# MCU.net
KiCad netlist of a schematic drawn in Altium Designer
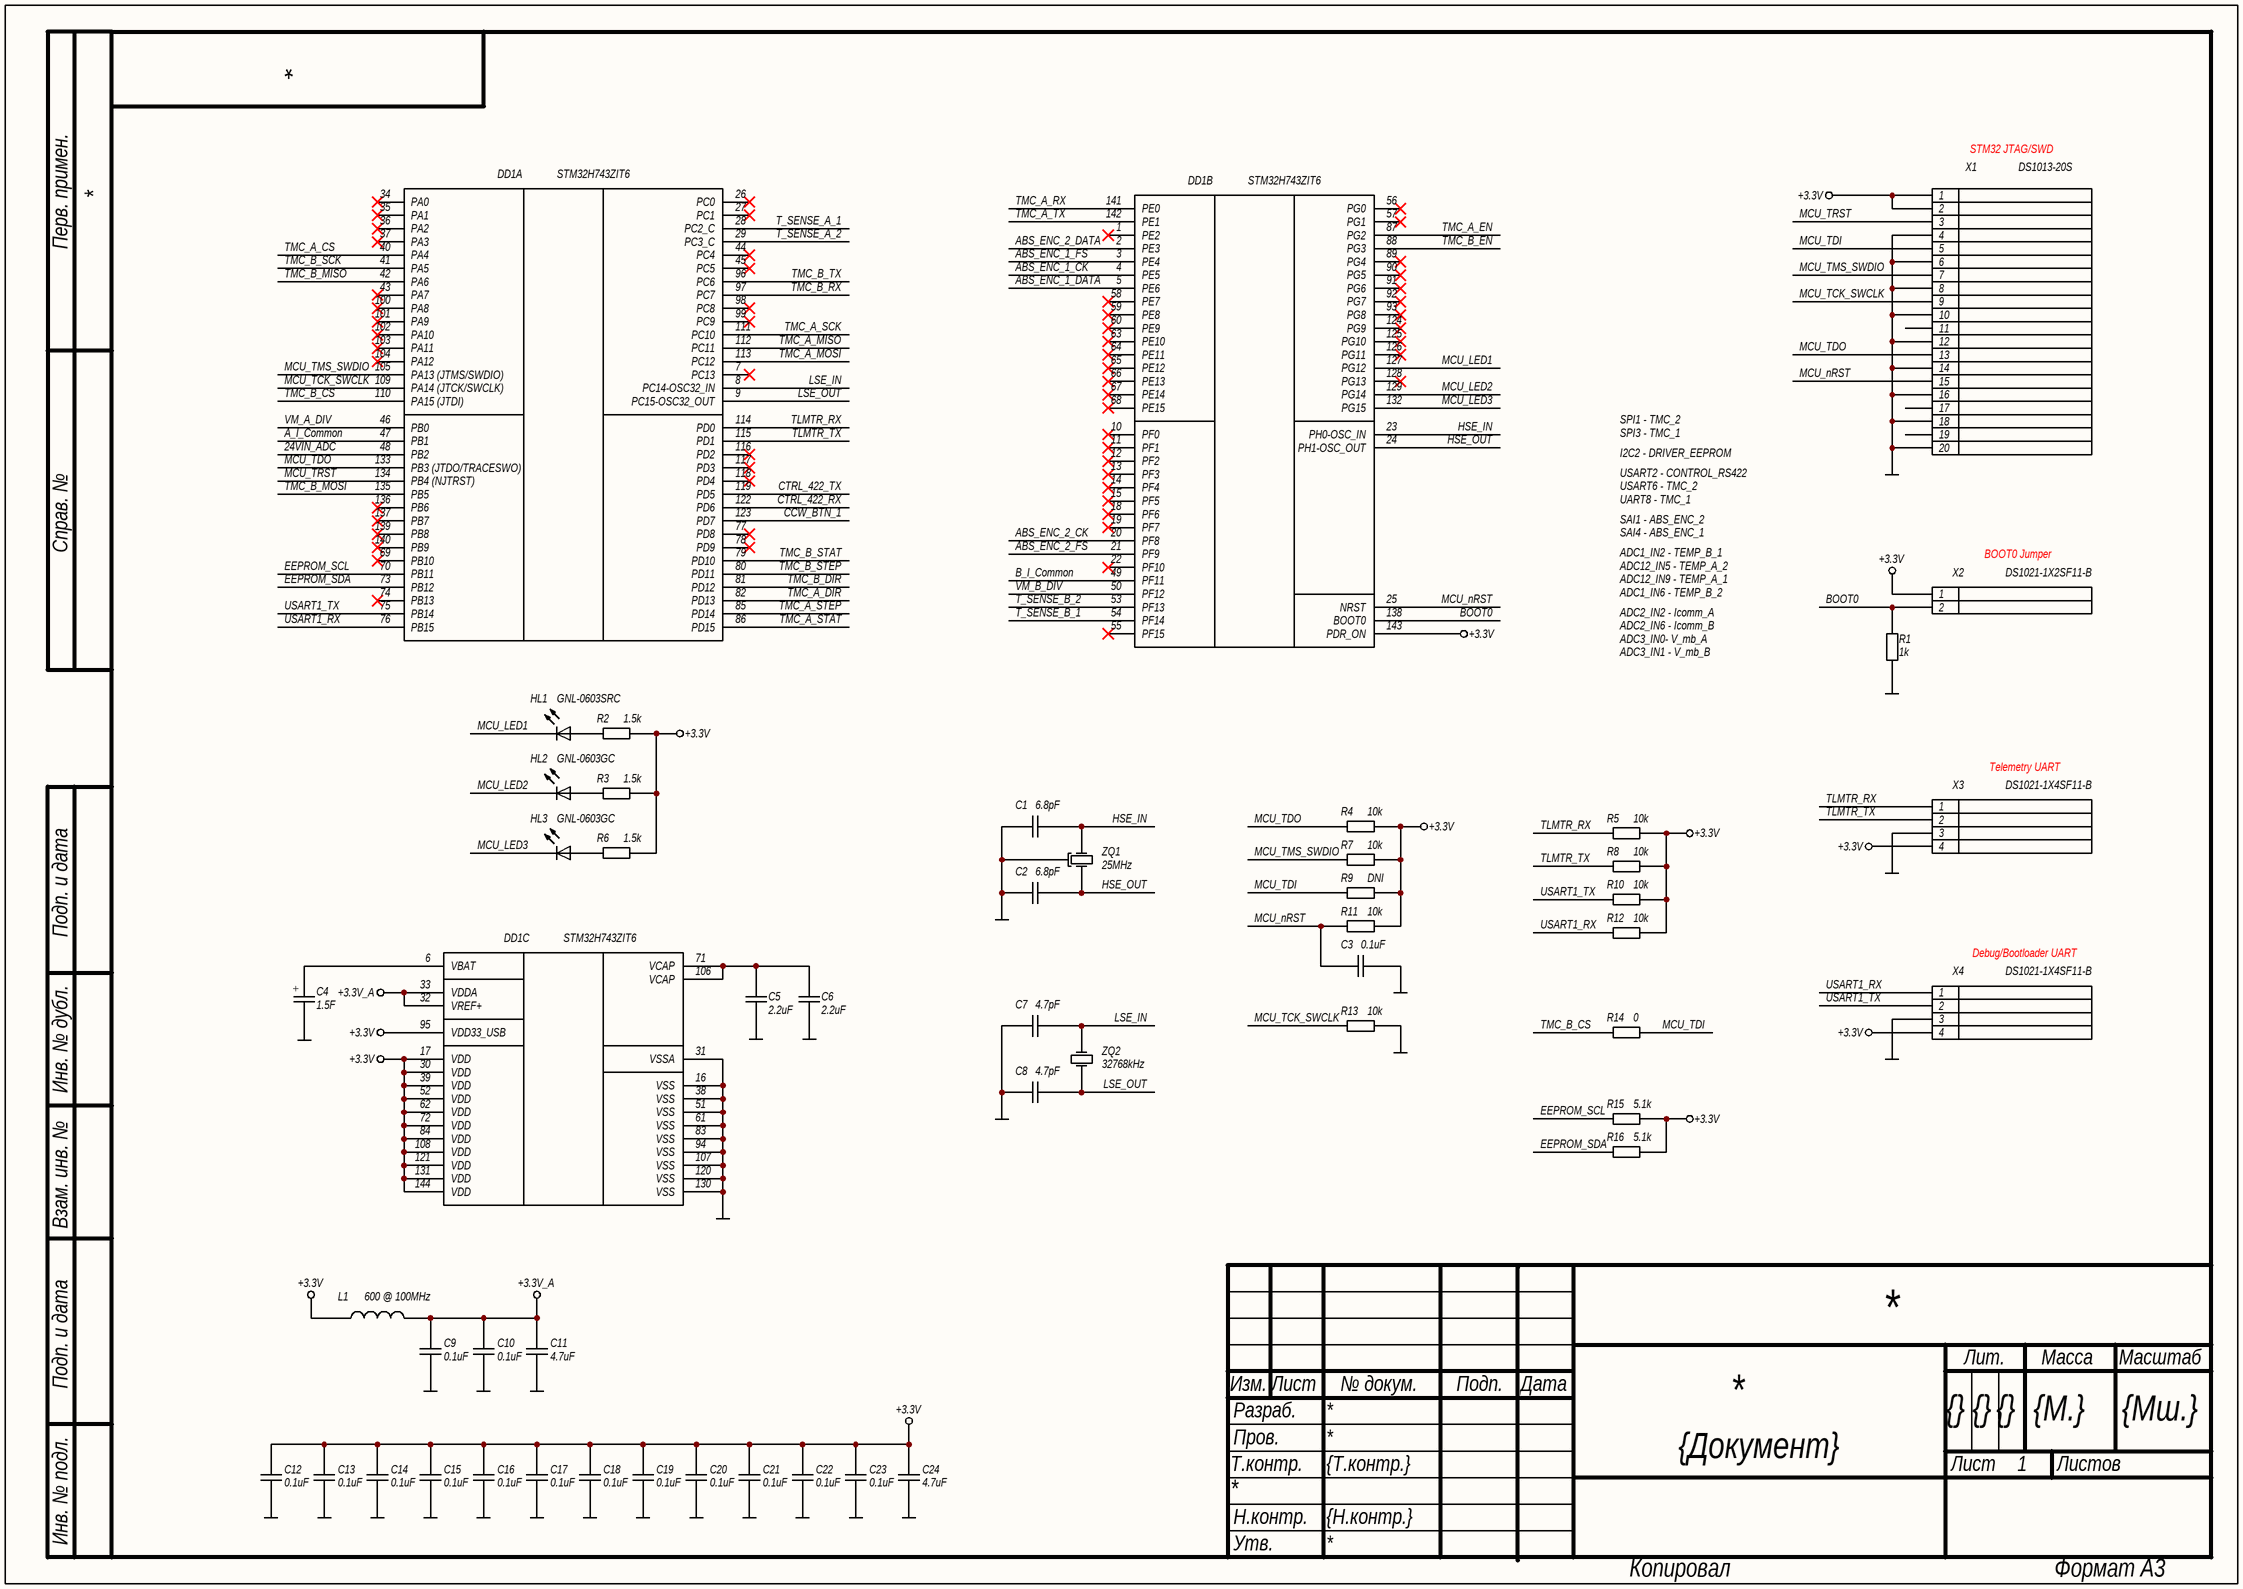
[diagram p0: MCU.SchDoc]

(export (version "E")
  (design (tool "Eeschema 10.0.6"))
  (components
    (comp (ref "C1")
      (value "6.8pF")
      (footprint "C0603N")
      (description "Конденсатор")
      (libsource (lib "Components Library") (part "CAP_FIXED"))
    )
    (comp (ref "C2")
      (value "6.8pF")
      (footprint "C0603N")
      (description "Конденсатор")
      (libsource (lib "Components Library") (part "CAP_FIXED"))
    )
    (comp (ref "C3")
      (value "0.1uF")
      (footprint "C0603N")
      (description "Конденсатор")
      (libsource (lib "Components Library") (part "CAP_FIXED"))
    )
    (comp (ref "C4")
      (value "1.5F")
      (footprint "KR-5R5H155-R")
      (description "Ионистор")
      (libsource (lib "Components Library") (part "CAP_EDLC"))
    )
    (comp (ref "C5")
      (value "2.2uF")
      (footprint "C0603N")
      (description "Конденсатор")
      (libsource (lib "Components Library") (part "CAP_FIXED"))
    )
    (comp (ref "C6")
      (value "2.2uF")
      (footprint "C0603N")
      (description "Конденсатор")
      (libsource (lib "Components Library") (part "CAP_FIXED"))
    )
    (comp (ref "C7")
      (value "4.7pF")
      (footprint "C0603N")
      (description "Конденсатор")
      (libsource (lib "Components Library") (part "CAP_FIXED"))
    )
    (comp (ref "C8")
      (value "4.7pF")
      (footprint "C0603N")
      (description "Конденсатор")
      (libsource (lib "Components Library") (part "CAP_FIXED"))
    )
    (comp (ref "C9")
      (value "0.1uF")
      (footprint "C0603N")
      (description "Конденсатор")
      (libsource (lib "Components Library") (part "CAP_FIXED"))
    )
    (comp (ref "C10")
      (value "0.1uF")
      (footprint "C0603N")
      (description "Конденсатор")
      (libsource (lib "Components Library") (part "CAP_FIXED"))
    )
    (comp (ref "C11")
      (value "4.7uF")
      (footprint "C0603N")
      (description "Конденсатор")
      (libsource (lib "Components Library") (part "CAP_FIXED"))
    )
    (comp (ref "C12")
      (value "0.1uF")
      (footprint "C0603N")
      (description "Конденсатор")
      (libsource (lib "Components Library") (part "CAP_FIXED"))
    )
    (comp (ref "C13")
      (value "0.1uF")
      (footprint "C0603N")
      (description "Конденсатор")
      (libsource (lib "Components Library") (part "CAP_FIXED"))
    )
    (comp (ref "C14")
      (value "0.1uF")
      (footprint "C0603N")
      (description "Конденсатор")
      (libsource (lib "Components Library") (part "CAP_FIXED"))
    )
    (comp (ref "C15")
      (value "0.1uF")
      (footprint "C0603N")
      (description "Конденсатор")
      (libsource (lib "Components Library") (part "CAP_FIXED"))
    )
    (comp (ref "C16")
      (value "0.1uF")
      (footprint "C0603N")
      (description "Конденсатор")
      (libsource (lib "Components Library") (part "CAP_FIXED"))
    )
    (comp (ref "C17")
      (value "0.1uF")
      (footprint "C0603N")
      (description "Конденсатор")
      (libsource (lib "Components Library") (part "CAP_FIXED"))
    )
    (comp (ref "C18")
      (value "0.1uF")
      (footprint "C0603N")
      (description "Конденсатор")
      (libsource (lib "Components Library") (part "CAP_FIXED"))
    )
    (comp (ref "C19")
      (value "0.1uF")
      (footprint "C0603N")
      (description "Конденсатор")
      (libsource (lib "Components Library") (part "CAP_FIXED"))
    )
    (comp (ref "C20")
      (value "0.1uF")
      (footprint "C0603N")
      (description "Конденсатор")
      (libsource (lib "Components Library") (part "CAP_FIXED"))
    )
    (comp (ref "C21")
      (value "0.1uF")
      (footprint "C0603N")
      (description "Конденсатор")
      (libsource (lib "Components Library") (part "CAP_FIXED"))
    )
    (comp (ref "C22")
      (value "0.1uF")
      (footprint "C0603N")
      (description "Конденсатор")
      (libsource (lib "Components Library") (part "CAP_FIXED"))
    )
    (comp (ref "C23")
      (value "0.1uF")
      (footprint "C0603N")
      (description "Конденсатор")
      (libsource (lib "Components Library") (part "CAP_FIXED"))
    )
    (comp (ref "C24")
      (value "4.7uF")
      (footprint "C0603N")
      (description "Конденсатор")
      (libsource (lib "Components Library") (part "CAP_FIXED"))
    )
    (comp (ref "DD1")
      (value "STM32H743ZIT6")
      (footprint "LQFP144")
      (description "Микросхема микроконтроллер")
      (libsource (lib "Components Library") (part "STM32H743ZxT"))
    )
    (comp (ref "HL1")
      (value "GNL-0603SRC")
      (footprint "LED0603")
      (description "Светодиод")
      (libsource (lib "Components Library") (part "LED"))
    )
    (comp (ref "HL2")
      (value "GNL-0603GC")
      (footprint "LED0603")
      (description "Светодиод")
      (libsource (lib "Components Library") (part "LED"))
    )
    (comp (ref "HL3")
      (value "GNL-0603GC")
      (footprint "LED0603")
      (description "Светодиод")
      (libsource (lib "Components Library") (part "LED"))
    )
    (comp (ref "L1")
      (value "600 @ 100MHz")
      (footprint "FB0603N")
      (description "Фильтр ЭМП индуктивный")
      (libsource (lib "Components Library") (part "IND_FILTER"))
    )
    (comp (ref "R1")
      (value "1k")
      (footprint "R0603N")
      (description "Резистор")
      (libsource (lib "") (part "RES_FIXED_2"))
    )
    (comp (ref "R2")
      (value "1.5k")
      (footprint "R0603N")
      (description "Резистор")
      (libsource (lib "Components Library") (part "RES_FIXED"))
    )
    (comp (ref "R3")
      (value "1.5k")
      (footprint "R0603N")
      (description "Резистор")
      (libsource (lib "Components Library") (part "RES_FIXED"))
    )
    (comp (ref "R4")
      (value "10k")
      (footprint "R0603N")
      (description "Резистор")
      (libsource (lib "Components Library") (part "RES_FIXED"))
    )
    (comp (ref "R5")
      (value "10k")
      (footprint "R0603N")
      (description "Резистор")
      (libsource (lib "Components Library") (part "RES_FIXED"))
    )
    (comp (ref "R6")
      (value "1.5k")
      (footprint "R0603N")
      (description "Резистор")
      (libsource (lib "Components Library") (part "RES_FIXED"))
    )
    (comp (ref "R7")
      (value "10k")
      (footprint "R0603N")
      (description "Резистор")
      (libsource (lib "Components Library") (part "RES_FIXED"))
    )
    (comp (ref "R8")
      (value "10k")
      (footprint "R0603N")
      (description "Резистор")
      (libsource (lib "Components Library") (part "RES_FIXED"))
    )
    (comp (ref "R9")
      (value "DNI")
      (footprint "R0603N")
      (description "Резистор")
      (libsource (lib "Components Library") (part "RES_FIXED"))
    )
    (comp (ref "R10")
      (value "10k")
      (footprint "R0603N")
      (description "Резистор")
      (libsource (lib "Components Library") (part "RES_FIXED"))
    )
    (comp (ref "R11")
      (value "10k")
      (footprint "R0603N")
      (description "Резистор")
      (libsource (lib "Components Library") (part "RES_FIXED"))
    )
    (comp (ref "R12")
      (value "10k")
      (footprint "R0603N")
      (description "Резистор")
      (libsource (lib "Components Library") (part "RES_FIXED"))
    )
    (comp (ref "R13")
      (value "10k")
      (footprint "R0603N")
      (description "Резистор")
      (libsource (lib "") (part "RES_FIXED_1"))
    )
    (comp (ref "R14")
      (value "0")
      (footprint "R0603N")
      (description "Резистор")
      (libsource (lib "") (part "RES_FIXED_2"))
    )
    (comp (ref "R15")
      (value "5.1k")
      (footprint "R0603N")
      (description "Резистор")
      (libsource (lib "Components Library") (part "RES_FIXED"))
    )
    (comp (ref "R16")
      (value "5.1k")
      (footprint "R0603N")
      (description "Резистор")
      (libsource (lib "Components Library") (part "RES_FIXED"))
    )
    (comp (ref "X1")
      (value "DS1013-20S")
      (footprint "2.54_2X10_HEADER_BOX")
      (description "Разъем, 20 контактов")
      (libsource (lib "Components Library") (part "Connector 20"))
    )
    (comp (ref "X2")
      (value "DS1021-1X2SF11-B")
      (footprint "2.54_2X1_HEADER")
      (description "Разъем, 2 контакта")
      (libsource (lib "Components Library") (part "Connector 2"))
    )
    (comp (ref "X3")
      (value "DS1021-1X4SF11-B")
      (footprint "2.54_4X1_HEADER")
      (description "Разъем, 4 контакта")
      (libsource (lib "Components Library") (part "Connector 4"))
    )
    (comp (ref "X4")
      (value "DS1021-1X4SF11-B")
      (footprint "2.54_4X1_HEADER")
      (description "Разъем, 4 контакта")
      (libsource (lib "Components Library") (part "Connector 4"))
    )
    (comp (ref "ZQ1")
      (value "25MHz")
      (footprint "NX3225GA")
      (description "Кварцевый резонатор, экранированный")
      (libsource (lib "Components Library") (part "RESONATOR_3PIN"))
    )
    (comp (ref "ZQ2")
      (value "32768kHz")
      (footprint "NX3215SA")
      (description "Кварцевый резонатор")
      (libsource (lib "Components Library") (part "RESONATOR"))
    )
  )
  (nets
    (net (code "1") (name "+3.3V") (class "Default")
      (node (ref "C12") (pin "2") (pinfunction "2_2") (pintype "passive"))
      (node (ref "C13") (pin "2") (pinfunction "2_2") (pintype "passive"))
      (node (ref "C14") (pin "2") (pinfunction "2_2") (pintype "passive"))
      (node (ref "C15") (pin "2") (pinfunction "2_2") (pintype "passive"))
      (node (ref "C16") (pin "2") (pinfunction "2_2") (pintype "passive"))
      (node (ref "C17") (pin "2") (pinfunction "2_2") (pintype "passive"))
      (node (ref "C18") (pin "2") (pinfunction "2_2") (pintype "passive"))
      (node (ref "C19") (pin "2") (pinfunction "2_2") (pintype "passive"))
      (node (ref "C20") (pin "2") (pinfunction "2_2") (pintype "passive"))
      (node (ref "C21") (pin "2") (pinfunction "2_2") (pintype "passive"))
      (node (ref "C22") (pin "2") (pinfunction "2_2") (pintype "passive"))
      (node (ref "C23") (pin "2") (pinfunction "2_2") (pintype "passive"))
      (node (ref "C24") (pin "2") (pinfunction "2_2") (pintype "passive"))
      (node (ref "DD1") (pin "108") (pinfunction "VDD_108") (pintype "power_in"))
      (node (ref "DD1") (pin "121") (pinfunction "VDD_121") (pintype "power_in"))
      (node (ref "DD1") (pin "131") (pinfunction "VDD_131") (pintype "power_in"))
      (node (ref "DD1") (pin "143") (pinfunction "PDR_ON_143") (pintype "power_in"))
      (node (ref "DD1") (pin "144") (pinfunction "VDD_144") (pintype "power_in"))
      (node (ref "DD1") (pin "17") (pinfunction "VDD_17") (pintype "power_in"))
      (node (ref "DD1") (pin "30") (pinfunction "VDD_30") (pintype "power_in"))
      (node (ref "DD1") (pin "39") (pinfunction "VDD_39") (pintype "power_in"))
      (node (ref "DD1") (pin "52") (pinfunction "VDD_52") (pintype "power_in"))
      (node (ref "DD1") (pin "62") (pinfunction "VDD_62") (pintype "power_in"))
      (node (ref "DD1") (pin "72") (pinfunction "VDD_72") (pintype "power_in"))
      (node (ref "DD1") (pin "84") (pinfunction "VDD_84") (pintype "power_in"))
      (node (ref "DD1") (pin "95") (pinfunction "VDD33_USB_95") (pintype "power_in"))
      (node (ref "L1") (pin "1") (pinfunction "1_1") (pintype "passive"))
      (node (ref "R10") (pin "1") (pinfunction "1_1") (pintype "passive"))
      (node (ref "R11") (pin "1") (pinfunction "1_1") (pintype "passive"))
      (node (ref "R12") (pin "1") (pinfunction "1_1") (pintype "passive"))
      (node (ref "R15") (pin "1") (pinfunction "1_1") (pintype "passive"))
      (node (ref "R16") (pin "1") (pinfunction "1_1") (pintype "passive"))
      (node (ref "R2") (pin "1") (pinfunction "1_1") (pintype "passive"))
      (node (ref "R3") (pin "1") (pinfunction "1_1") (pintype "passive"))
      (node (ref "R4") (pin "1") (pinfunction "1_1") (pintype "passive"))
      (node (ref "R5") (pin "1") (pinfunction "1_1") (pintype "passive"))
      (node (ref "R6") (pin "1") (pinfunction "1_1") (pintype "passive"))
      (node (ref "R7") (pin "1") (pinfunction "1_1") (pintype "passive"))
      (node (ref "R8") (pin "1") (pinfunction "1_1") (pintype "passive"))
      (node (ref "R9") (pin "1") (pinfunction "1_1") (pintype "passive"))
      (node (ref "X1") (pin "1") (pinfunction "1_1") (pintype "power_in"))
      (node (ref "X1") (pin "2") (pinfunction "2_2") (pintype "power_in"))
      (node (ref "X2") (pin "1") (pinfunction "1_1") (pintype "power_in"))
      (node (ref "X3") (pin "4") (pinfunction "4_4") (pintype "power_in"))
      (node (ref "X4") (pin "4") (pinfunction "4_4") (pintype "power_in"))
    )
    (net (code "2") (name "+3.3V_A") (class "Default")
      (node (ref "C10") (pin "2") (pinfunction "2_2") (pintype "passive"))
      (node (ref "C11") (pin "2") (pinfunction "2_2") (pintype "passive"))
      (node (ref "C9") (pin "2") (pinfunction "2_2") (pintype "passive"))
      (node (ref "DD1") (pin "32") (pinfunction "VREF+_32") (pintype "power_in"))
      (node (ref "DD1") (pin "33") (pinfunction "VDDA_33") (pintype "power_in"))
      (node (ref "L1") (pin "2") (pinfunction "2_2") (pintype "passive"))
    )
    (net (code "3") (name "/24VIN_ADC") (class "Default")
      (node (ref "DD1") (pin "48") (pinfunction "PB2_48") (pintype "power_in"))
    )
    (net (code "4") (name "/ABS_ENC_1_CK") (class "Default")
      (node (ref "DD1") (pin "4") (pinfunction "PE5_4") (pintype "power_in"))
    )
    (net (code "5") (name "/ABS_ENC_1_DATA") (class "Default")
      (node (ref "DD1") (pin "5") (pinfunction "PE6_5") (pintype "power_in"))
    )
    (net (code "6") (name "/ABS_ENC_1_FS") (class "Default")
      (node (ref "DD1") (pin "3") (pinfunction "PE4_3") (pintype "power_in"))
    )
    (net (code "7") (name "/ABS_ENC_2_CK") (class "Default")
      (node (ref "DD1") (pin "20") (pinfunction "PF8_20") (pintype "power_in"))
    )
    (net (code "8") (name "/ABS_ENC_2_DATA") (class "Default")
      (node (ref "DD1") (pin "2") (pinfunction "PE3_2") (pintype "power_in"))
    )
    (net (code "9") (name "/ABS_ENC_2_FS") (class "Default")
      (node (ref "DD1") (pin "21") (pinfunction "PF9_21") (pintype "power_in"))
    )
    (net (code "10") (name "/A_I_Common") (class "Default")
      (node (ref "DD1") (pin "47") (pinfunction "PB1_47") (pintype "power_in"))
    )
    (net (code "11") (name "/BOOT0") (class "Default")
      (node (ref "DD1") (pin "138") (pinfunction "BOOT0_138") (pintype "power_in"))
      (node (ref "R1") (pin "1") (pinfunction "1_1") (pintype "passive"))
      (node (ref "X2") (pin "2") (pinfunction "2_2") (pintype "power_in"))
    )
    (net (code "12") (name "/B_I_Common") (class "Default")
      (node (ref "DD1") (pin "49") (pinfunction "PF11_49") (pintype "power_in"))
    )
    (net (code "13") (name "/CCW_BTN_1") (class "Default")
      (node (ref "DD1") (pin "123") (pinfunction "PD7_123") (pintype "power_in"))
    )
    (net (code "14") (name "/CTRL_422_RX") (class "Default")
      (node (ref "DD1") (pin "122") (pinfunction "PD6_122") (pintype "power_in"))
    )
    (net (code "15") (name "/CTRL_422_TX") (class "Default")
      (node (ref "DD1") (pin "119") (pinfunction "PD5_119") (pintype "power_in"))
    )
    (net (code "16") (name "/EEPROM_SCL") (class "Default")
      (node (ref "DD1") (pin "70") (pinfunction "PB11_70") (pintype "power_in"))
      (node (ref "R15") (pin "2") (pinfunction "2_2") (pintype "passive"))
    )
    (net (code "17") (name "/EEPROM_SDA") (class "Default")
      (node (ref "DD1") (pin "73") (pinfunction "PB12_73") (pintype "power_in"))
      (node (ref "R16") (pin "2") (pinfunction "2_2") (pintype "passive"))
    )
    (net (code "18") (name "/HSE_IN") (class "Default")
      (node (ref "C1") (pin "1") (pinfunction "1_1") (pintype "passive"))
      (node (ref "DD1") (pin "23") (pinfunction "PH0-OSC_IN_23") (pintype "power_in"))
      (node (ref "ZQ1") (pin "1") (pinfunction "1_1") (pintype "passive"))
    )
    (net (code "19") (name "/HSE_OUT") (class "Default")
      (node (ref "C2") (pin "1") (pinfunction "1_1") (pintype "passive"))
      (node (ref "DD1") (pin "24") (pinfunction "PH1-OSC_OUT_24") (pintype "power_in"))
      (node (ref "ZQ1") (pin "3") (pinfunction "3_3") (pintype "passive"))
    )
    (net (code "20") (name "/LSE_IN") (class "Default")
      (node (ref "C7") (pin "1") (pinfunction "1_1") (pintype "passive"))
      (node (ref "DD1") (pin "8") (pinfunction "PC14-OSC32_IN_8") (pintype "power_in"))
      (node (ref "ZQ2") (pin "2") (pinfunction "2_2") (pintype "passive"))
    )
    (net (code "21") (name "/LSE_OUT") (class "Default")
      (node (ref "C8") (pin "1") (pinfunction "1_1") (pintype "passive"))
      (node (ref "DD1") (pin "9") (pinfunction "PC15-OSC32_OUT_9") (pintype "power_in"))
      (node (ref "ZQ2") (pin "1") (pinfunction "1_1") (pintype "passive"))
    )
    (net (code "22") (name "/MCU_LED1") (class "Default")
      (node (ref "DD1") (pin "127") (pinfunction "PG12_127") (pintype "power_in"))
      (node (ref "HL1") (pin "1") (pinfunction "K_1") (pintype "passive"))
    )
    (net (code "23") (name "/MCU_LED2") (class "Default")
      (node (ref "DD1") (pin "129") (pinfunction "PG14_129") (pintype "power_in"))
      (node (ref "HL2") (pin "1") (pinfunction "K_1") (pintype "passive"))
    )
    (net (code "24") (name "/MCU_LED3") (class "Default")
      (node (ref "DD1") (pin "132") (pinfunction "PG15_132") (pintype "power_in"))
      (node (ref "HL3") (pin "1") (pinfunction "K_1") (pintype "passive"))
    )
    (net (code "25") (name "/MCU_TCK_SWCLK") (class "Default")
      (node (ref "DD1") (pin "109") (pinfunction "PA14_(JTCK/SWCLK)_109") (pintype "power_in"))
      (node (ref "R13") (pin "1") (pinfunction "1_1") (pintype "passive"))
      (node (ref "X1") (pin "9") (pinfunction "9_9") (pintype "power_in"))
    )
    (net (code "26") (name "/MCU_TDI") (class "Default")
      (node (ref "R14") (pin "1") (pinfunction "1_1") (pintype "passive"))
      (node (ref "R9") (pin "2") (pinfunction "2_2") (pintype "passive"))
      (node (ref "X1") (pin "5") (pinfunction "5_5") (pintype "power_in"))
    )
    (net (code "27") (name "/MCU_TDO") (class "Default")
      (node (ref "DD1") (pin "133") (pinfunction "PB3_(JTDO/TRACESWO)_133") (pintype "power_in"))
      (node (ref "R4") (pin "2") (pinfunction "2_2") (pintype "passive"))
      (node (ref "X1") (pin "13") (pinfunction "13_13") (pintype "power_in"))
    )
    (net (code "28") (name "/MCU_TMS_SWDIO") (class "Default")
      (node (ref "DD1") (pin "105") (pinfunction "PA13_(JTMS/SWDIO)_105") (pintype "power_in"))
      (node (ref "R7") (pin "2") (pinfunction "2_2") (pintype "passive"))
      (node (ref "X1") (pin "7") (pinfunction "7_7") (pintype "power_in"))
    )
    (net (code "29") (name "/MCU_TRST") (class "Default")
      (node (ref "DD1") (pin "134") (pinfunction "PB4_(NJTRST)_134") (pintype "power_in"))
      (node (ref "X1") (pin "3") (pinfunction "3_3") (pintype "power_in"))
    )
    (net (code "30") (name "/MCU_nRST") (class "Default")
      (node (ref "C3") (pin "2") (pinfunction "2_2") (pintype "passive"))
      (node (ref "DD1") (pin "25") (pinfunction "NRST_25") (pintype "power_in"))
      (node (ref "R11") (pin "2") (pinfunction "2_2") (pintype "passive"))
      (node (ref "X1") (pin "15") (pinfunction "15_15") (pintype "power_in"))
    )
    (net (code "31") (name "/TLMTR_RX") (class "Default")
      (node (ref "DD1") (pin "114") (pinfunction "PD0_114") (pintype "power_in"))
      (node (ref "R5") (pin "2") (pinfunction "2_2") (pintype "passive"))
      (node (ref "X3") (pin "1") (pinfunction "1_1") (pintype "power_in"))
    )
    (net (code "32") (name "/TLMTR_TX") (class "Default")
      (node (ref "DD1") (pin "115") (pinfunction "PD1_115") (pintype "power_in"))
      (node (ref "R8") (pin "2") (pinfunction "2_2") (pintype "passive"))
      (node (ref "X3") (pin "2") (pinfunction "2_2") (pintype "power_in"))
    )
    (net (code "33") (name "/TMC_A_CS") (class "Default")
      (node (ref "DD1") (pin "40") (pinfunction "PA4_40") (pintype "power_in"))
    )
    (net (code "34") (name "/TMC_A_DIR") (class "Default")
      (node (ref "DD1") (pin "82") (pinfunction "PD13_82") (pintype "power_in"))
    )
    (net (code "35") (name "/TMC_A_EN") (class "Default")
      (node (ref "DD1") (pin "87") (pinfunction "PG2_87") (pintype "power_in"))
    )
    (net (code "36") (name "/TMC_A_MISO") (class "Default")
      (node (ref "DD1") (pin "112") (pinfunction "PC11_112") (pintype "power_in"))
    )
    (net (code "37") (name "/TMC_A_MOSI") (class "Default")
      (node (ref "DD1") (pin "113") (pinfunction "PC12_113") (pintype "power_in"))
    )
    (net (code "38") (name "/TMC_A_RX") (class "Default")
      (node (ref "DD1") (pin "141") (pinfunction "PE0_141") (pintype "power_in"))
    )
    (net (code "39") (name "/TMC_A_SCK") (class "Default")
      (node (ref "DD1") (pin "111") (pinfunction "PC10_111") (pintype "power_in"))
    )
    (net (code "40") (name "/TMC_A_STAT") (class "Default")
      (node (ref "DD1") (pin "86") (pinfunction "PD15_86") (pintype "power_in"))
    )
    (net (code "41") (name "/TMC_A_STEP") (class "Default")
      (node (ref "DD1") (pin "85") (pinfunction "PD14_85") (pintype "power_in"))
    )
    (net (code "42") (name "/TMC_A_TX") (class "Default")
      (node (ref "DD1") (pin "142") (pinfunction "PE1_142") (pintype "power_in"))
    )
    (net (code "43") (name "/TMC_B_CS") (class "Default")
      (node (ref "DD1") (pin "110") (pinfunction "PA15_(JTDI)_110") (pintype "power_in"))
      (node (ref "R14") (pin "2") (pinfunction "2_2") (pintype "passive"))
    )
    (net (code "44") (name "/TMC_B_DIR") (class "Default")
      (node (ref "DD1") (pin "81") (pinfunction "PD12_81") (pintype "power_in"))
    )
    (net (code "45") (name "/TMC_B_EN") (class "Default")
      (node (ref "DD1") (pin "88") (pinfunction "PG3_88") (pintype "power_in"))
    )
    (net (code "46") (name "/TMC_B_MISO") (class "Default")
      (node (ref "DD1") (pin "42") (pinfunction "PA6_42") (pintype "power_in"))
    )
    (net (code "47") (name "/TMC_B_MOSI") (class "Default")
      (node (ref "DD1") (pin "135") (pinfunction "PB5_135") (pintype "power_in"))
    )
    (net (code "48") (name "/TMC_B_RX") (class "Default")
      (node (ref "DD1") (pin "97") (pinfunction "PC7_97") (pintype "power_in"))
    )
    (net (code "49") (name "/TMC_B_SCK") (class "Default")
      (node (ref "DD1") (pin "41") (pinfunction "PA5_41") (pintype "power_in"))
    )
    (net (code "50") (name "/TMC_B_STAT") (class "Default")
      (node (ref "DD1") (pin "79") (pinfunction "PD10_79") (pintype "power_in"))
    )
    (net (code "51") (name "/TMC_B_STEP") (class "Default")
      (node (ref "DD1") (pin "80") (pinfunction "PD11_80") (pintype "power_in"))
    )
    (net (code "52") (name "/TMC_B_TX") (class "Default")
      (node (ref "DD1") (pin "96") (pinfunction "PC6_96") (pintype "power_in"))
    )
    (net (code "53") (name "/T_SENSE_A_1") (class "Default")
      (node (ref "DD1") (pin "28") (pinfunction "PC2_C_28") (pintype "power_in"))
    )
    (net (code "54") (name "/T_SENSE_A_2") (class "Default")
      (node (ref "DD1") (pin "29") (pinfunction "PC3_C_29") (pintype "power_in"))
    )
    (net (code "55") (name "/T_SENSE_B_1") (class "Default")
      (node (ref "DD1") (pin "54") (pinfunction "PF14_54") (pintype "power_in"))
    )
    (net (code "56") (name "/T_SENSE_B_2") (class "Default")
      (node (ref "DD1") (pin "53") (pinfunction "PF13_53") (pintype "power_in"))
    )
    (net (code "57") (name "/USART1_RX") (class "Default")
      (node (ref "DD1") (pin "76") (pinfunction "PB15_76") (pintype "power_in"))
      (node (ref "R12") (pin "2") (pinfunction "2_2") (pintype "passive"))
      (node (ref "X4") (pin "1") (pinfunction "1_1") (pintype "power_in"))
    )
    (net (code "58") (name "/USART1_TX") (class "Default")
      (node (ref "DD1") (pin "75") (pinfunction "PB14_75") (pintype "power_in"))
      (node (ref "R10") (pin "2") (pinfunction "2_2") (pintype "passive"))
      (node (ref "X4") (pin "2") (pinfunction "2_2") (pintype "power_in"))
    )
    (net (code "59") (name "/VM_A_DIV") (class "Default")
      (node (ref "DD1") (pin "46") (pinfunction "PB0_46") (pintype "power_in"))
    )
    (net (code "60") (name "/VM_B_DIV") (class "Default")
      (node (ref "DD1") (pin "50") (pinfunction "PF12_50") (pintype "power_in"))
    )
    (net (code "61") (name "GND") (class "Default")
      (node (ref "C1") (pin "2") (pinfunction "2_2") (pintype "passive"))
      (node (ref "C10") (pin "1") (pinfunction "1_1") (pintype "passive"))
      (node (ref "C11") (pin "1") (pinfunction "1_1") (pintype "passive"))
      (node (ref "C12") (pin "1") (pinfunction "1_1") (pintype "passive"))
      (node (ref "C13") (pin "1") (pinfunction "1_1") (pintype "passive"))
      (node (ref "C14") (pin "1") (pinfunction "1_1") (pintype "passive"))
      (node (ref "C15") (pin "1") (pinfunction "1_1") (pintype "passive"))
      (node (ref "C16") (pin "1") (pinfunction "1_1") (pintype "passive"))
      (node (ref "C17") (pin "1") (pinfunction "1_1") (pintype "passive"))
      (node (ref "C18") (pin "1") (pinfunction "1_1") (pintype "passive"))
      (node (ref "C19") (pin "1") (pinfunction "1_1") (pintype "passive"))
      (node (ref "C2") (pin "2") (pinfunction "2_2") (pintype "passive"))
      (node (ref "C20") (pin "1") (pinfunction "1_1") (pintype "passive"))
      (node (ref "C21") (pin "1") (pinfunction "1_1") (pintype "passive"))
      (node (ref "C22") (pin "1") (pinfunction "1_1") (pintype "passive"))
      (node (ref "C23") (pin "1") (pinfunction "1_1") (pintype "passive"))
      (node (ref "C24") (pin "1") (pinfunction "1_1") (pintype "passive"))
      (node (ref "C3") (pin "1") (pinfunction "1_1") (pintype "passive"))
      (node (ref "C4") (pin "1") (pinfunction "1_1") (pintype "passive"))
      (node (ref "C5") (pin "1") (pinfunction "1_1") (pintype "passive"))
      (node (ref "C6") (pin "1") (pinfunction "1_1") (pintype "passive"))
      (node (ref "C7") (pin "2") (pinfunction "2_2") (pintype "passive"))
      (node (ref "C8") (pin "2") (pinfunction "2_2") (pintype "passive"))
      (node (ref "C9") (pin "1") (pinfunction "1_1") (pintype "passive"))
      (node (ref "DD1") (pin "107") (pinfunction "VSS_107") (pintype "power_in"))
      (node (ref "DD1") (pin "120") (pinfunction "VSS_120") (pintype "power_in"))
      (node (ref "DD1") (pin "130") (pinfunction "VSS_130") (pintype "power_in"))
      (node (ref "DD1") (pin "16") (pinfunction "VSS_16") (pintype "power_in"))
      (node (ref "DD1") (pin "31") (pinfunction "VSSA_31") (pintype "power_in"))
      (node (ref "DD1") (pin "38") (pinfunction "VSS_38") (pintype "power_in"))
      (node (ref "DD1") (pin "51") (pinfunction "VSS_51") (pintype "power_in"))
      (node (ref "DD1") (pin "61") (pinfunction "VSS_61") (pintype "power_in"))
      (node (ref "DD1") (pin "83") (pinfunction "VSS_83") (pintype "power_in"))
      (node (ref "DD1") (pin "94") (pinfunction "VSS_94") (pintype "power_in"))
      (node (ref "R1") (pin "2") (pinfunction "2_2") (pintype "passive"))
      (node (ref "R13") (pin "2") (pinfunction "2_2") (pintype "passive"))
      (node (ref "X1") (pin "10") (pinfunction "10_10") (pintype "power_in"))
      (node (ref "X1") (pin "12") (pinfunction "12_12") (pintype "power_in"))
      (node (ref "X1") (pin "14") (pinfunction "14_14") (pintype "power_in"))
      (node (ref "X1") (pin "16") (pinfunction "16_16") (pintype "power_in"))
      (node (ref "X1") (pin "18") (pinfunction "18_18") (pintype "power_in"))
      (node (ref "X1") (pin "20") (pinfunction "20_20") (pintype "power_in"))
      (node (ref "X1") (pin "4") (pinfunction "4_4") (pintype "power_in"))
      (node (ref "X1") (pin "6") (pinfunction "6_6") (pintype "power_in"))
      (node (ref "X1") (pin "8") (pinfunction "8_8") (pintype "power_in"))
      (node (ref "X3") (pin "3") (pinfunction "3_3") (pintype "power_in"))
      (node (ref "X4") (pin "3") (pinfunction "3_3") (pintype "power_in"))
      (node (ref "ZQ1") (pin "2") (pinfunction "2_2") (pintype "passive"))
    )
    (net (code "62") (name "Net-(C5-Pad2)") (class "Default")
      (node (ref "C5") (pin "2") (pinfunction "2_2") (pintype "passive"))
      (node (ref "C6") (pin "2") (pinfunction "2_2") (pintype "passive"))
      (node (ref "DD1") (pin "106") (pinfunction "VCAP_106") (pintype "power_in"))
      (node (ref "DD1") (pin "71") (pinfunction "VCAP_71") (pintype "power_in"))
    )
    (net (code "63") (name "Net-(DD1C-VBAT)") (class "Default")
      (node (ref "C4") (pin "2") (pinfunction "2_2") (pintype "passive"))
      (node (ref "DD1") (pin "6") (pinfunction "VBAT_6") (pintype "power_in"))
    )
    (net (code "64") (name "Net-(HL1-A)") (class "Default")
      (node (ref "HL1") (pin "2") (pinfunction "A_2") (pintype "passive"))
      (node (ref "R2") (pin "2") (pinfunction "2_2") (pintype "passive"))
    )
    (net (code "65") (name "Net-(HL2-A)") (class "Default")
      (node (ref "HL2") (pin "2") (pinfunction "A_2") (pintype "passive"))
      (node (ref "R3") (pin "2") (pinfunction "2_2") (pintype "passive"))
    )
    (net (code "66") (name "Net-(HL3-A)") (class "Default")
      (node (ref "HL3") (pin "2") (pinfunction "A_2") (pintype "passive"))
      (node (ref "R6") (pin "2") (pinfunction "2_2") (pintype "passive"))
    )
    (net (code "67") (name "unconnected-(DD1A-PA0-Pad34)") (class "Default")
      (node (ref "DD1") (pin "34") (pinfunction "PA0_34") (pintype "power_in+no_connect"))
    )
    (net (code "68") (name "unconnected-(DD1A-PA1-Pad35)") (class "Default")
      (node (ref "DD1") (pin "35") (pinfunction "PA1_35") (pintype "power_in+no_connect"))
    )
    (net (code "69") (name "unconnected-(DD1A-PA2-Pad36)") (class "Default")
      (node (ref "DD1") (pin "36") (pinfunction "PA2_36") (pintype "power_in+no_connect"))
    )
    (net (code "70") (name "unconnected-(DD1A-PA3-Pad37)") (class "Default")
      (node (ref "DD1") (pin "37") (pinfunction "PA3_37") (pintype "power_in+no_connect"))
    )
    (net (code "71") (name "unconnected-(DD1A-PA7-Pad43)") (class "Default")
      (node (ref "DD1") (pin "43") (pinfunction "PA7_43") (pintype "power_in+no_connect"))
    )
    (net (code "72") (name "unconnected-(DD1A-PA8-Pad100)") (class "Default")
      (node (ref "DD1") (pin "100") (pinfunction "PA8_100") (pintype "power_in+no_connect"))
    )
    (net (code "73") (name "unconnected-(DD1A-PA9-Pad101)") (class "Default")
      (node (ref "DD1") (pin "101") (pinfunction "PA9_101") (pintype "power_in+no_connect"))
    )
    (net (code "74") (name "unconnected-(DD1A-PA10-Pad102)") (class "Default")
      (node (ref "DD1") (pin "102") (pinfunction "PA10_102") (pintype "power_in+no_connect"))
    )
    (net (code "75") (name "unconnected-(DD1A-PA11-Pad103)") (class "Default")
      (node (ref "DD1") (pin "103") (pinfunction "PA11_103") (pintype "power_in+no_connect"))
    )
    (net (code "76") (name "unconnected-(DD1A-PA12-Pad104)") (class "Default")
      (node (ref "DD1") (pin "104") (pinfunction "PA12_104") (pintype "power_in+no_connect"))
    )
    (net (code "77") (name "unconnected-(DD1A-PB6-Pad136)") (class "Default")
      (node (ref "DD1") (pin "136") (pinfunction "PB6_136") (pintype "power_in+no_connect"))
    )
    (net (code "78") (name "unconnected-(DD1A-PB7-Pad137)") (class "Default")
      (node (ref "DD1") (pin "137") (pinfunction "PB7_137") (pintype "power_in+no_connect"))
    )
    (net (code "79") (name "unconnected-(DD1A-PB8-Pad139)") (class "Default")
      (node (ref "DD1") (pin "139") (pinfunction "PB8_139") (pintype "power_in+no_connect"))
    )
    (net (code "80") (name "unconnected-(DD1A-PB9-Pad140)") (class "Default")
      (node (ref "DD1") (pin "140") (pinfunction "PB9_140") (pintype "power_in+no_connect"))
    )
    (net (code "81") (name "unconnected-(DD1A-PB10-Pad69)") (class "Default")
      (node (ref "DD1") (pin "69") (pinfunction "PB10_69") (pintype "power_in+no_connect"))
    )
    (net (code "82") (name "unconnected-(DD1A-PB13-Pad74)") (class "Default")
      (node (ref "DD1") (pin "74") (pinfunction "PB13_74") (pintype "power_in+no_connect"))
    )
    (net (code "83") (name "unconnected-(DD1A-PC0-Pad26)") (class "Default")
      (node (ref "DD1") (pin "26") (pinfunction "PC0_26") (pintype "power_in+no_connect"))
    )
    (net (code "84") (name "unconnected-(DD1A-PC1-Pad27)") (class "Default")
      (node (ref "DD1") (pin "27") (pinfunction "PC1_27") (pintype "power_in+no_connect"))
    )
    (net (code "85") (name "unconnected-(DD1A-PC4-Pad44)") (class "Default")
      (node (ref "DD1") (pin "44") (pinfunction "PC4_44") (pintype "power_in+no_connect"))
    )
    (net (code "86") (name "unconnected-(DD1A-PC5-Pad45)") (class "Default")
      (node (ref "DD1") (pin "45") (pinfunction "PC5_45") (pintype "power_in+no_connect"))
    )
    (net (code "87") (name "unconnected-(DD1A-PC8-Pad98)") (class "Default")
      (node (ref "DD1") (pin "98") (pinfunction "PC8_98") (pintype "power_in+no_connect"))
    )
    (net (code "88") (name "unconnected-(DD1A-PC9-Pad99)") (class "Default")
      (node (ref "DD1") (pin "99") (pinfunction "PC9_99") (pintype "power_in+no_connect"))
    )
    (net (code "89") (name "unconnected-(DD1A-PC13-Pad7)") (class "Default")
      (node (ref "DD1") (pin "7") (pinfunction "PC13_7") (pintype "power_in+no_connect"))
    )
    (net (code "90") (name "unconnected-(DD1A-PD2-Pad116)") (class "Default")
      (node (ref "DD1") (pin "116") (pinfunction "PD2_116") (pintype "power_in+no_connect"))
    )
    (net (code "91") (name "unconnected-(DD1A-PD3-Pad117)") (class "Default")
      (node (ref "DD1") (pin "117") (pinfunction "PD3_117") (pintype "power_in+no_connect"))
    )
    (net (code "92") (name "unconnected-(DD1A-PD4-Pad118)") (class "Default")
      (node (ref "DD1") (pin "118") (pinfunction "PD4_118") (pintype "power_in+no_connect"))
    )
    (net (code "93") (name "unconnected-(DD1A-PD8-Pad77)") (class "Default")
      (node (ref "DD1") (pin "77") (pinfunction "PD8_77") (pintype "power_in+no_connect"))
    )
    (net (code "94") (name "unconnected-(DD1A-PD9-Pad78)") (class "Default")
      (node (ref "DD1") (pin "78") (pinfunction "PD9_78") (pintype "power_in+no_connect"))
    )
    (net (code "95") (name "unconnected-(DD1B-PE2-Pad1)") (class "Default")
      (node (ref "DD1") (pin "1") (pinfunction "PE2_1") (pintype "power_in+no_connect"))
    )
    (net (code "96") (name "unconnected-(DD1B-PE7-Pad58)") (class "Default")
      (node (ref "DD1") (pin "58") (pinfunction "PE7_58") (pintype "power_in+no_connect"))
    )
    (net (code "97") (name "unconnected-(DD1B-PE8-Pad59)") (class "Default")
      (node (ref "DD1") (pin "59") (pinfunction "PE8_59") (pintype "power_in+no_connect"))
    )
    (net (code "98") (name "unconnected-(DD1B-PE9-Pad60)") (class "Default")
      (node (ref "DD1") (pin "60") (pinfunction "PE9_60") (pintype "power_in+no_connect"))
    )
    (net (code "99") (name "unconnected-(DD1B-PE10-Pad63)") (class "Default")
      (node (ref "DD1") (pin "63") (pinfunction "PE10_63") (pintype "power_in+no_connect"))
    )
    (net (code "100") (name "unconnected-(DD1B-PE11-Pad64)") (class "Default")
      (node (ref "DD1") (pin "64") (pinfunction "PE11_64") (pintype "power_in+no_connect"))
    )
    (net (code "101") (name "unconnected-(DD1B-PE12-Pad65)") (class "Default")
      (node (ref "DD1") (pin "65") (pinfunction "PE12_65") (pintype "power_in+no_connect"))
    )
    (net (code "102") (name "unconnected-(DD1B-PE13-Pad66)") (class "Default")
      (node (ref "DD1") (pin "66") (pinfunction "PE13_66") (pintype "power_in+no_connect"))
    )
    (net (code "103") (name "unconnected-(DD1B-PE14-Pad67)") (class "Default")
      (node (ref "DD1") (pin "67") (pinfunction "PE14_67") (pintype "power_in+no_connect"))
    )
    (net (code "104") (name "unconnected-(DD1B-PE15-Pad68)") (class "Default")
      (node (ref "DD1") (pin "68") (pinfunction "PE15_68") (pintype "power_in+no_connect"))
    )
    (net (code "105") (name "unconnected-(DD1B-PF0-Pad10)") (class "Default")
      (node (ref "DD1") (pin "10") (pinfunction "PF0_10") (pintype "power_in+no_connect"))
    )
    (net (code "106") (name "unconnected-(DD1B-PF1-Pad11)") (class "Default")
      (node (ref "DD1") (pin "11") (pinfunction "PF1_11") (pintype "power_in+no_connect"))
    )
    (net (code "107") (name "unconnected-(DD1B-PF2-Pad12)") (class "Default")
      (node (ref "DD1") (pin "12") (pinfunction "PF2_12") (pintype "power_in+no_connect"))
    )
    (net (code "108") (name "unconnected-(DD1B-PF3-Pad13)") (class "Default")
      (node (ref "DD1") (pin "13") (pinfunction "PF3_13") (pintype "power_in+no_connect"))
    )
    (net (code "109") (name "unconnected-(DD1B-PF4-Pad14)") (class "Default")
      (node (ref "DD1") (pin "14") (pinfunction "PF4_14") (pintype "power_in+no_connect"))
    )
    (net (code "110") (name "unconnected-(DD1B-PF5-Pad15)") (class "Default")
      (node (ref "DD1") (pin "15") (pinfunction "PF5_15") (pintype "power_in+no_connect"))
    )
    (net (code "111") (name "unconnected-(DD1B-PF6-Pad18)") (class "Default")
      (node (ref "DD1") (pin "18") (pinfunction "PF6_18") (pintype "power_in+no_connect"))
    )
    (net (code "112") (name "unconnected-(DD1B-PF7-Pad19)") (class "Default")
      (node (ref "DD1") (pin "19") (pinfunction "PF7_19") (pintype "power_in+no_connect"))
    )
    (net (code "113") (name "unconnected-(DD1B-PF10-Pad22)") (class "Default")
      (node (ref "DD1") (pin "22") (pinfunction "PF10_22") (pintype "power_in+no_connect"))
    )
    (net (code "114") (name "unconnected-(DD1B-PF15-Pad55)") (class "Default")
      (node (ref "DD1") (pin "55") (pinfunction "PF15_55") (pintype "power_in+no_connect"))
    )
    (net (code "115") (name "unconnected-(DD1B-PG0-Pad56)") (class "Default")
      (node (ref "DD1") (pin "56") (pinfunction "PG0_56") (pintype "power_in+no_connect"))
    )
    (net (code "116") (name "unconnected-(DD1B-PG1-Pad57)") (class "Default")
      (node (ref "DD1") (pin "57") (pinfunction "PG1_57") (pintype "power_in+no_connect"))
    )
    (net (code "117") (name "unconnected-(DD1B-PG4-Pad89)") (class "Default")
      (node (ref "DD1") (pin "89") (pinfunction "PG4_89") (pintype "power_in+no_connect"))
    )
    (net (code "118") (name "unconnected-(DD1B-PG5-Pad90)") (class "Default")
      (node (ref "DD1") (pin "90") (pinfunction "PG5_90") (pintype "power_in+no_connect"))
    )
    (net (code "119") (name "unconnected-(DD1B-PG6-Pad91)") (class "Default")
      (node (ref "DD1") (pin "91") (pinfunction "PG6_91") (pintype "power_in+no_connect"))
    )
    (net (code "120") (name "unconnected-(DD1B-PG7-Pad92)") (class "Default")
      (node (ref "DD1") (pin "92") (pinfunction "PG7_92") (pintype "power_in+no_connect"))
    )
    (net (code "121") (name "unconnected-(DD1B-PG8-Pad93)") (class "Default")
      (node (ref "DD1") (pin "93") (pinfunction "PG8_93") (pintype "power_in+no_connect"))
    )
    (net (code "122") (name "unconnected-(DD1B-PG9-Pad124)") (class "Default")
      (node (ref "DD1") (pin "124") (pinfunction "PG9_124") (pintype "power_in+no_connect"))
    )
    (net (code "123") (name "unconnected-(DD1B-PG10-Pad125)") (class "Default")
      (node (ref "DD1") (pin "125") (pinfunction "PG10_125") (pintype "power_in+no_connect"))
    )
    (net (code "124") (name "unconnected-(DD1B-PG11-Pad126)") (class "Default")
      (node (ref "DD1") (pin "126") (pinfunction "PG11_126") (pintype "power_in+no_connect"))
    )
    (net (code "125") (name "unconnected-(DD1B-PG13-Pad128)") (class "Default")
      (node (ref "DD1") (pin "128") (pinfunction "PG13_128") (pintype "power_in+no_connect"))
    )
    (net (code "126") (name "unconnected-(X1-Pad11)") (class "Default")
      (node (ref "X1") (pin "11") (pinfunction "11_11") (pintype "power_in"))
    )
    (net (code "127") (name "unconnected-(X1-Pad17)") (class "Default")
      (node (ref "X1") (pin "17") (pinfunction "17_17") (pintype "power_in"))
    )
    (net (code "128") (name "unconnected-(X1-Pad19)") (class "Default")
      (node (ref "X1") (pin "19") (pinfunction "19_19") (pintype "power_in"))
    )
  )
)
